# ft231x-breakout-v11-openSX70versionSEEED.net
KiCad netlist of a schematic drawn in EAGLE
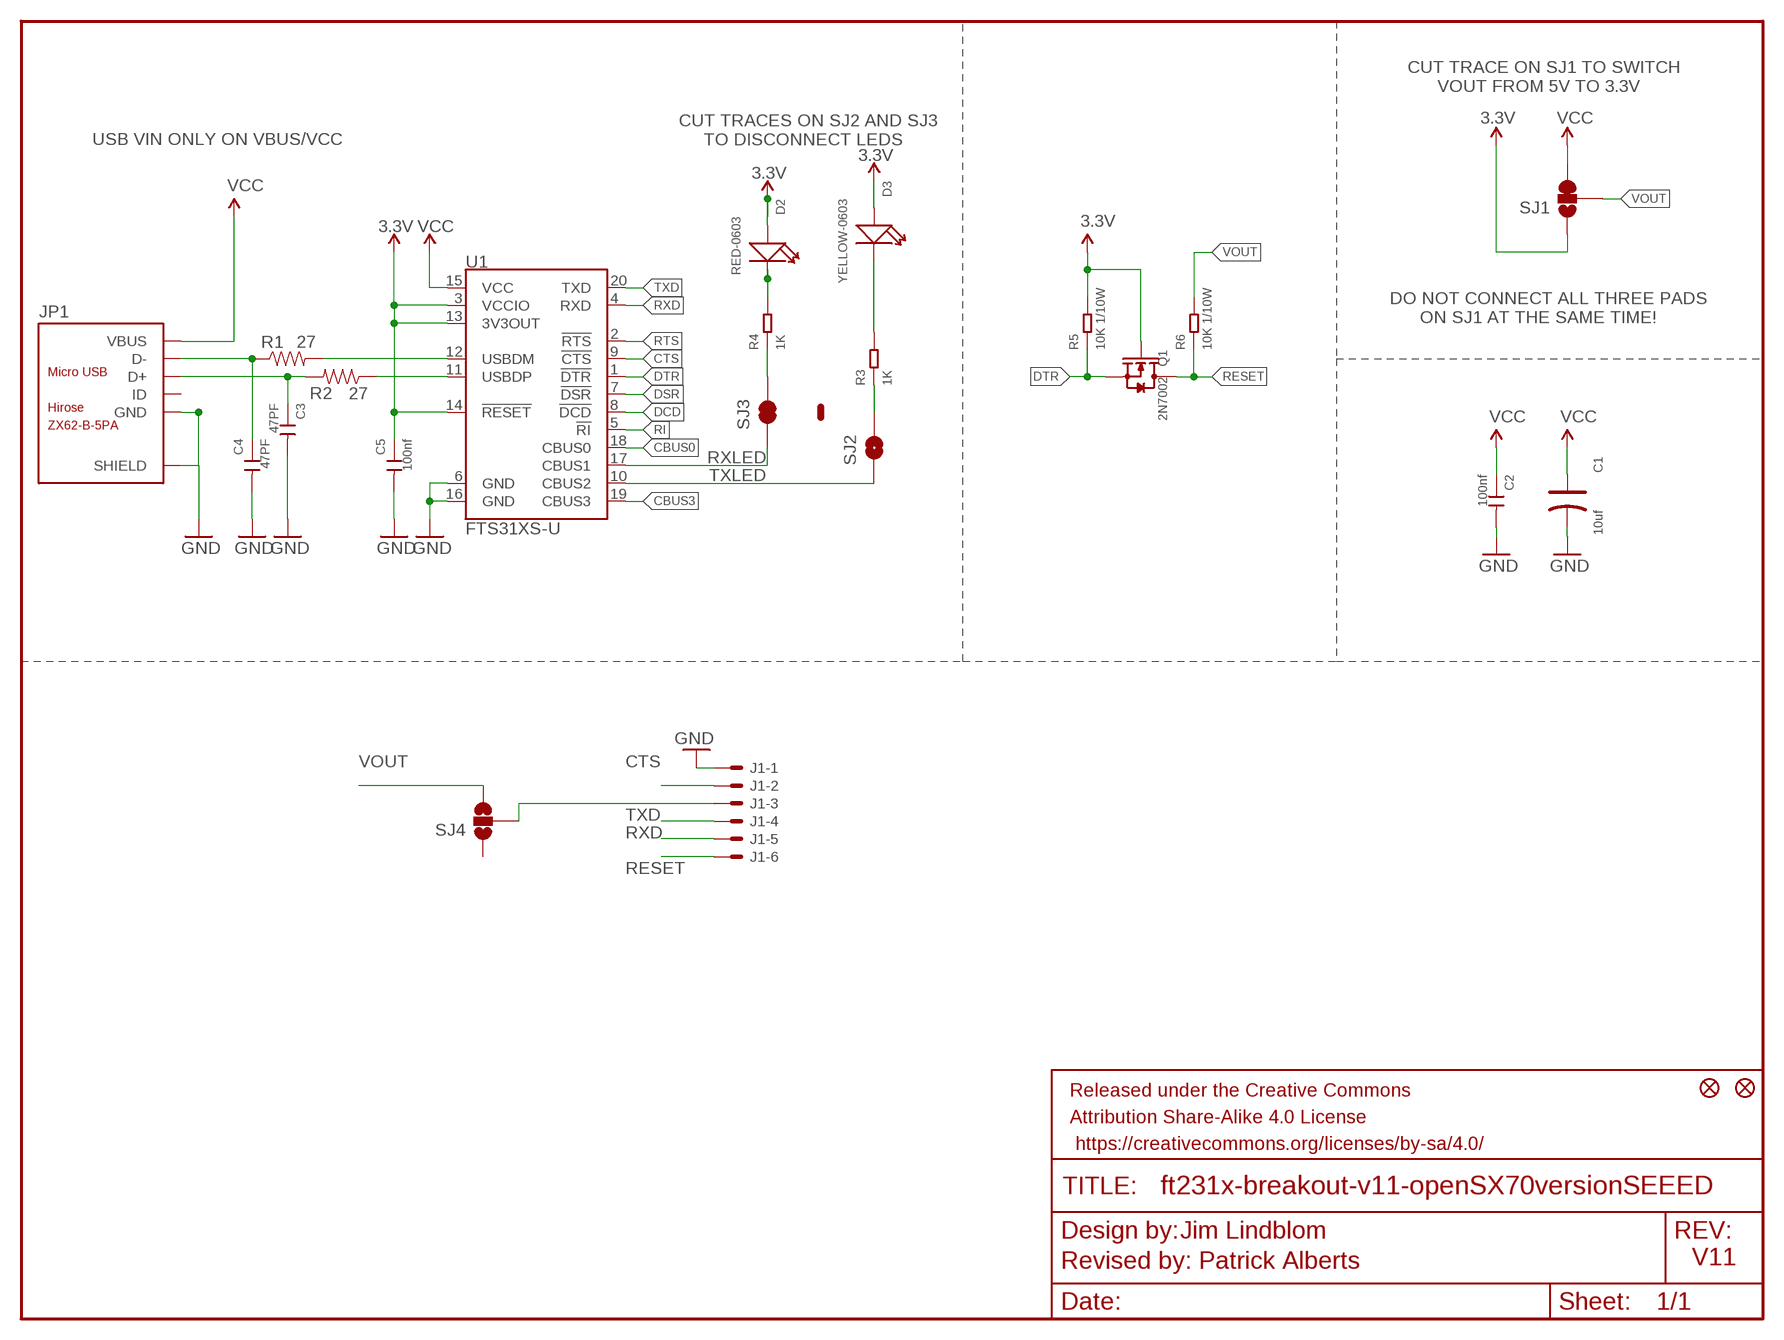
[diagram p0: schematic, sheet 1]

(export (version "E")
  (design (tool "Eeschema 10.0.6"))
  (components
    (comp (ref "C1")
      (value "10uf")
      (footprint "eagle-import:AVX-B")
      (fields (field (name "MPN") "TAJB106K016RNJ"))
      (libsource (lib "eagle-import") (part "TANTALUM-SMD-10UF-16V-10%(AVX-B)"))
    )
    (comp (ref "C2")
      (value "100nf")
      (footprint "eagle-import:C0603")
      (fields (field (name "MPN") "CC0603KRX7R9BB104"))
      (libsource (lib "eagle-import") (part "CERAMIC-100NF-50V-10%-X7R(0603)"))
    )
    (comp (ref "C3")
      (value "47PF")
      (footprint "eagle-import:C0402")
      (fields (field (name "MPN") "CC0402JRNPO9BN470"))
      (libsource (lib "eagle-import") (part "CERAMIC-47PF-50V-5%-NP0(0402)"))
    )
    (comp (ref "C4")
      (value "47PF")
      (footprint "eagle-import:C0402")
      (fields (field (name "MPN") "CC0402JRNPO9BN470"))
      (libsource (lib "eagle-import") (part "CERAMIC-47PF-50V-5%-NP0(0402)"))
    )
    (comp (ref "C5")
      (value "100nf")
      (footprint "eagle-import:C0603")
      (fields (field (name "MPN") "CC0603KRX7R9BB104"))
      (libsource (lib "eagle-import") (part "CERAMIC-100NF-50V-10%-X7R(0603)"))
    )
    (comp (ref "D2")
      (value "RED-0603")
      (footprint "eagle-import:LED-0603")
      (fields (field (name "MPN") "19-217-R6C-AL1M2VY-3T"))
      (libsource (lib "eagle-import") (part "LED-SMD-RED-DIFFUSED(0603)"))
    )
    (comp (ref "D3")
      (value "YELLOW-0603")
      (footprint "eagle-import:LED-0603")
      (fields (field (name "MPN") "19-217-Y5C-AM1N1VY-3T"))
      (libsource (lib "eagle-import") (part "SMD-LED-CLEAR-YELLOW(0603)"))
    )
    (comp (ref "FRAME1")
      (value "FRAME-LETTER")
      (footprint "eagle-import:CREATIVE_COMMONS")
      (libsource (lib "eagle-import") (part "FRAME-LETTER"))
    )
    (comp (ref "J1")
      (value "XF2L-0625-1")
      (footprint "eagle-import:XF2L-0625-1")
      (fields (field (name "MF") "OMRON COMPONENTS USA"))
      (libsource (lib "eagle-import") (part "XF2-06?25-1L"))
    )
    (comp (ref "JP1")
      (value "ZX62-B-5PA")
      (footprint "eagle-import:MICRO-USB5+6P-SMD-0.65-AB")
      (libsource (lib "eagle-import") (part "MICRO-USB-SMD(ZX62-B-5PA)"))
    )
    (comp (ref "JP5")
      (value "FIDUCIAL1X2")
      (footprint "eagle-import:FIDUCIAL-1X2")
      (libsource (lib "eagle-import") (part "FIDUCIAL1X2"))
    )
    (comp (ref "JP6")
      (value "FIDUCIAL1X2")
      (footprint "eagle-import:FIDUCIAL-1X2")
      (libsource (lib "eagle-import") (part "FIDUCIAL1X2"))
    )
    (comp (ref "Q1")
      (value "2N7002")
      (footprint "eagle-import:SOT-23")
      (fields (field (name "MPN") "2N7002,215"))
      (libsource (lib "eagle-import") (part "SMD-MOSFET-N-CH-60V-300MA-LOGIC-LEVEL-FET-2N7002(SOT-23)"))
    )
    (comp (ref "R1")
      (value "27")
      (footprint "eagle-import:0603-RES")
      (libsource (lib "eagle-import") (part "27OHM1/10W1%(0603)0603-RES"))
    )
    (comp (ref "R2")
      (value "27")
      (footprint "eagle-import:0603-RES")
      (libsource (lib "eagle-import") (part "27OHM1/10W1%(0603)0603-RES"))
    )
    (comp (ref "R3")
      (value "1K")
      (footprint "eagle-import:R0603")
      (fields (field (name "MPN") "RC0603FR-071KL"))
      (libsource (lib "eagle-import") (part "SMD-RES-1K-1%-1/10W(0603)"))
    )
    (comp (ref "R4")
      (value "1K")
      (footprint "eagle-import:R0603")
      (fields (field (name "MPN") "RC0603FR-071KL"))
      (libsource (lib "eagle-import") (part "SMD-RES-1K-1%-1/10W(0603)"))
    )
    (comp (ref "R5")
      (value "10K 1/10W")
      (footprint "eagle-import:R0603")
      (fields (field (name "MPN") "RC0603JR-0710KL"))
      (libsource (lib "eagle-import") (part "SMD-RES-10K-5%-1/10W(0603)"))
    )
    (comp (ref "R6")
      (value "10K 1/10W")
      (footprint "eagle-import:R0603")
      (fields (field (name "MPN") "RC0603JR-0710KL"))
      (libsource (lib "eagle-import") (part "SMD-RES-10K-5%-1/10W(0603)"))
    )
    (comp (ref "SJ1")
      (value "SOLDERJUMPER_2WAYS")
      (footprint "eagle-import:SJ_3")
      (libsource (lib "eagle-import") (part "SOLDERJUMPER_2WAYS"))
    )
    (comp (ref "SJ2")
      (value "TXLED")
      (footprint "eagle-import:SJ_2S-TRACE")
      (libsource (lib "eagle-import") (part "SOLDERJUMPERTRACE"))
    )
    (comp (ref "SJ3")
      (value "RXLED")
      (footprint "eagle-import:PAD-JUMPER-2-NC_BY_TRACE_YES_SILK")
      (libsource (lib "eagle-import") (part "JUMPER-PAD-2-NC_BY_TRACE"))
    )
    (comp (ref "SJ4")
      (value "SOLDERJUMPER_2WAYS")
      (footprint "eagle-import:SJ_3")
      (libsource (lib "eagle-import") (part "SOLDERJUMPER_2WAYS"))
    )
    (comp (ref "U1")
      (value "FTS31XS-U")
      (footprint "eagle-import:SSOP20_L")
      (libsource (lib "eagle-import") (part "FT231XS"))
    )
  )
  (nets
    (net (code "1") (name "/RXLED") (class "Default")
      (node (ref "SJ3") (pin "1") (pinfunction "1_1") (pintype "passive"))
      (node (ref "U1") (pin "17") (pinfunction "CBUS1_17") (pintype "bidirectional"))
    )
    (net (code "2") (name "/TXLED") (class "Default")
      (node (ref "SJ2") (pin "1") (pinfunction "1_1") (pintype "passive"))
      (node (ref "U1") (pin "10") (pinfunction "CBUS2_10") (pintype "bidirectional"))
    )
    (net (code "3") (name "3.3V") (class "Default")
      (node (ref "C5") (pin "1") (pinfunction "1_1") (pintype "passive"))
      (node (ref "D2") (pin "+") (pinfunction "+_+") (pintype "passive"))
      (node (ref "D3") (pin "+") (pinfunction "+_+") (pintype "passive"))
      (node (ref "Q1") (pin "1") (pinfunction "G_1") (pintype "passive"))
      (node (ref "R5") (pin "2") (pinfunction "2_2") (pintype "passive"))
      (node (ref "SJ1") (pin "1") (pinfunction "1_1") (pintype "passive"))
      (node (ref "U1") (pin "13") (pinfunction "3V3OUT_13") (pintype "bidirectional"))
      (node (ref "U1") (pin "14") (pinfunction "~{RESET}_14") (pintype "bidirectional"))
      (node (ref "U1") (pin "3") (pinfunction "VCCIO_3") (pintype "bidirectional"))
    )
    (net (code "4") (name "CBUS0") (class "Default")
      (node (ref "U1") (pin "18") (pinfunction "CBUS0_18") (pintype "bidirectional"))
    )
    (net (code "5") (name "CBUS3") (class "Default")
      (node (ref "U1") (pin "19") (pinfunction "CBUS3_19") (pintype "bidirectional"))
    )
    (net (code "6") (name "CTS") (class "Default")
      (node (ref "J1") (pin "2") (pinfunction "MS_2") (pintype "passive"))
      (node (ref "U1") (pin "9") (pinfunction "~{CTS}_9") (pintype "bidirectional"))
    )
    (net (code "7") (name "DCD") (class "Default")
      (node (ref "U1") (pin "8") (pinfunction "~{DCD}_8") (pintype "bidirectional"))
    )
    (net (code "8") (name "DSR") (class "Default")
      (node (ref "U1") (pin "7") (pinfunction "~{DSR}_7") (pintype "bidirectional"))
    )
    (net (code "9") (name "DTR") (class "Default")
      (node (ref "Q1") (pin "2") (pinfunction "S_2") (pintype "passive"))
      (node (ref "R5") (pin "1") (pinfunction "1_1") (pintype "passive"))
      (node (ref "U1") (pin "1") (pinfunction "~{DTR}_1") (pintype "bidirectional"))
    )
    (net (code "10") (name "GND") (class "Default")
      (node (ref "C1") (pin "-") (pinfunction "-_-") (pintype "passive"))
      (node (ref "C2") (pin "2") (pinfunction "2_2") (pintype "passive"))
      (node (ref "C3") (pin "2") (pinfunction "2_2") (pintype "passive"))
      (node (ref "C4") (pin "2") (pinfunction "2_2") (pintype "passive"))
      (node (ref "C5") (pin "2") (pinfunction "2_2") (pintype "passive"))
      (node (ref "J1") (pin "1") (pinfunction "MS_1") (pintype "passive"))
      (node (ref "JP1") (pin "5") (pinfunction "GND_5") (pintype "power_in"))
      (node (ref "JP1") (pin "P1") (pinfunction "SHIELD_P1") (pintype "power_in"))
      (node (ref "JP1") (pin "P2") (pinfunction "SHIELD_P2") (pintype "power_in"))
      (node (ref "JP1") (pin "P3_1") (pinfunction "SHIELD_P3_1") (pintype "power_in"))
      (node (ref "JP1") (pin "P3_2") (pinfunction "SHIELD_P3_2") (pintype "power_in"))
      (node (ref "JP1") (pin "P3_3") (pinfunction "SHIELD_P3_3") (pintype "power_in"))
      (node (ref "JP1") (pin "P4_1") (pinfunction "SHIELD_P4_1") (pintype "power_in"))
      (node (ref "JP1") (pin "P4_2") (pinfunction "SHIELD_P4_2") (pintype "power_in"))
      (node (ref "JP1") (pin "P4_3") (pinfunction "SHIELD_P4_3") (pintype "power_in"))
      (node (ref "JP1") (pin "P5") (pinfunction "SHIELD_P5") (pintype "power_in"))
      (node (ref "JP1") (pin "P6") (pinfunction "SHIELD_P6") (pintype "power_in"))
      (node (ref "U1") (pin "16") (pinfunction "GND_16") (pintype "bidirectional"))
      (node (ref "U1") (pin "6") (pinfunction "GND_6") (pintype "bidirectional"))
    )
    (net (code "11") (name "Net-(D2-Pad-)") (class "Default")
      (node (ref "D2") (pin "-") (pinfunction "-_-") (pintype "passive"))
      (node (ref "R4") (pin "2") (pinfunction "2_2") (pintype "passive"))
    )
    (net (code "12") (name "Net-(D3-Pad-)") (class "Default")
      (node (ref "D3") (pin "-") (pinfunction "-_-") (pintype "passive"))
      (node (ref "R3") (pin "2") (pinfunction "2_2") (pintype "passive"))
    )
    (net (code "13") (name "Net-(J1C-MS)") (class "Default")
      (node (ref "J1") (pin "3") (pinfunction "MS_3") (pintype "passive"))
      (node (ref "SJ4") (pin "2") (pinfunction "2_2") (pintype "passive"))
    )
    (net (code "14") (name "Net-(JP1-D+)") (class "Default")
      (node (ref "C3") (pin "1") (pinfunction "1_1") (pintype "passive"))
      (node (ref "JP1") (pin "3") (pinfunction "D+_3") (pintype "bidirectional"))
      (node (ref "R2") (pin "2") (pinfunction "2_2") (pintype "passive"))
    )
    (net (code "15") (name "Net-(JP1-D-)") (class "Default")
      (node (ref "C4") (pin "1") (pinfunction "1_1") (pintype "passive"))
      (node (ref "JP1") (pin "2") (pinfunction "D-_2") (pintype "bidirectional"))
      (node (ref "R1") (pin "1") (pinfunction "1_1") (pintype "passive"))
    )
    (net (code "16") (name "Net-(R3-Pad1)") (class "Default")
      (node (ref "R3") (pin "1") (pinfunction "1_1") (pintype "passive"))
      (node (ref "SJ2") (pin "2") (pinfunction "2_2") (pintype "passive"))
    )
    (net (code "17") (name "Net-(R4-Pad1)") (class "Default")
      (node (ref "R4") (pin "1") (pinfunction "1_1") (pintype "passive"))
      (node (ref "SJ3") (pin "2") (pinfunction "2_2") (pintype "passive"))
    )
    (net (code "18") (name "Net-(U1-USBDM)") (class "Default")
      (node (ref "R1") (pin "2") (pinfunction "2_2") (pintype "passive"))
      (node (ref "U1") (pin "12") (pinfunction "USBDM_12") (pintype "bidirectional"))
    )
    (net (code "19") (name "Net-(U1-USBDP)") (class "Default")
      (node (ref "R2") (pin "1") (pinfunction "1_1") (pintype "passive"))
      (node (ref "U1") (pin "11") (pinfunction "USBDP_11") (pintype "bidirectional"))
    )
    (net (code "20") (name "RESET") (class "Default")
      (node (ref "J1") (pin "6") (pinfunction "MS_6") (pintype "passive"))
      (node (ref "Q1") (pin "3") (pinfunction "D_3") (pintype "passive"))
      (node (ref "R6") (pin "1") (pinfunction "1_1") (pintype "passive"))
    )
    (net (code "21") (name "RI") (class "Default")
      (node (ref "U1") (pin "5") (pinfunction "~{RI}_5") (pintype "bidirectional"))
    )
    (net (code "22") (name "RTS") (class "Default")
      (node (ref "U1") (pin "2") (pinfunction "~{RTS}_2") (pintype "bidirectional"))
    )
    (net (code "23") (name "RXD") (class "Default")
      (node (ref "J1") (pin "5") (pinfunction "MS_5") (pintype "passive"))
      (node (ref "U1") (pin "4") (pinfunction "RXD_4") (pintype "bidirectional"))
    )
    (net (code "24") (name "TXD") (class "Default")
      (node (ref "J1") (pin "4") (pinfunction "MS_4") (pintype "passive"))
      (node (ref "U1") (pin "20") (pinfunction "TXD_20") (pintype "bidirectional"))
    )
    (net (code "25") (name "VCC") (class "Default")
      (node (ref "C1") (pin "+") (pinfunction "+_+") (pintype "passive"))
      (node (ref "C2") (pin "1") (pinfunction "1_1") (pintype "passive"))
      (node (ref "JP1") (pin "1") (pinfunction "VBUS_1") (pintype "power_in"))
      (node (ref "SJ1") (pin "3") (pinfunction "3_3") (pintype "passive"))
      (node (ref "U1") (pin "15") (pinfunction "VCC_15") (pintype "bidirectional"))
    )
    (net (code "26") (name "VOUT") (class "Default")
      (node (ref "R6") (pin "2") (pinfunction "2_2") (pintype "passive"))
      (node (ref "SJ1") (pin "2") (pinfunction "2_2") (pintype "passive"))
      (node (ref "SJ4") (pin "3") (pinfunction "3_3") (pintype "passive"))
    )
    (net (code "27") (name "unconnected-(JP1-ID-Pad4)") (class "Default")
      (node (ref "JP1") (pin "4") (pinfunction "ID_4") (pintype "bidirectional"))
    )
    (net (code "28") (name "unconnected-(SJ4-Pad1)") (class "Default")
      (node (ref "SJ4") (pin "1") (pinfunction "1_1") (pintype "passive"))
    )
  )
)
